# Wedding_Centerpiece_Controller_V1_2.net
KiCad netlist of a schematic drawn in EAGLE
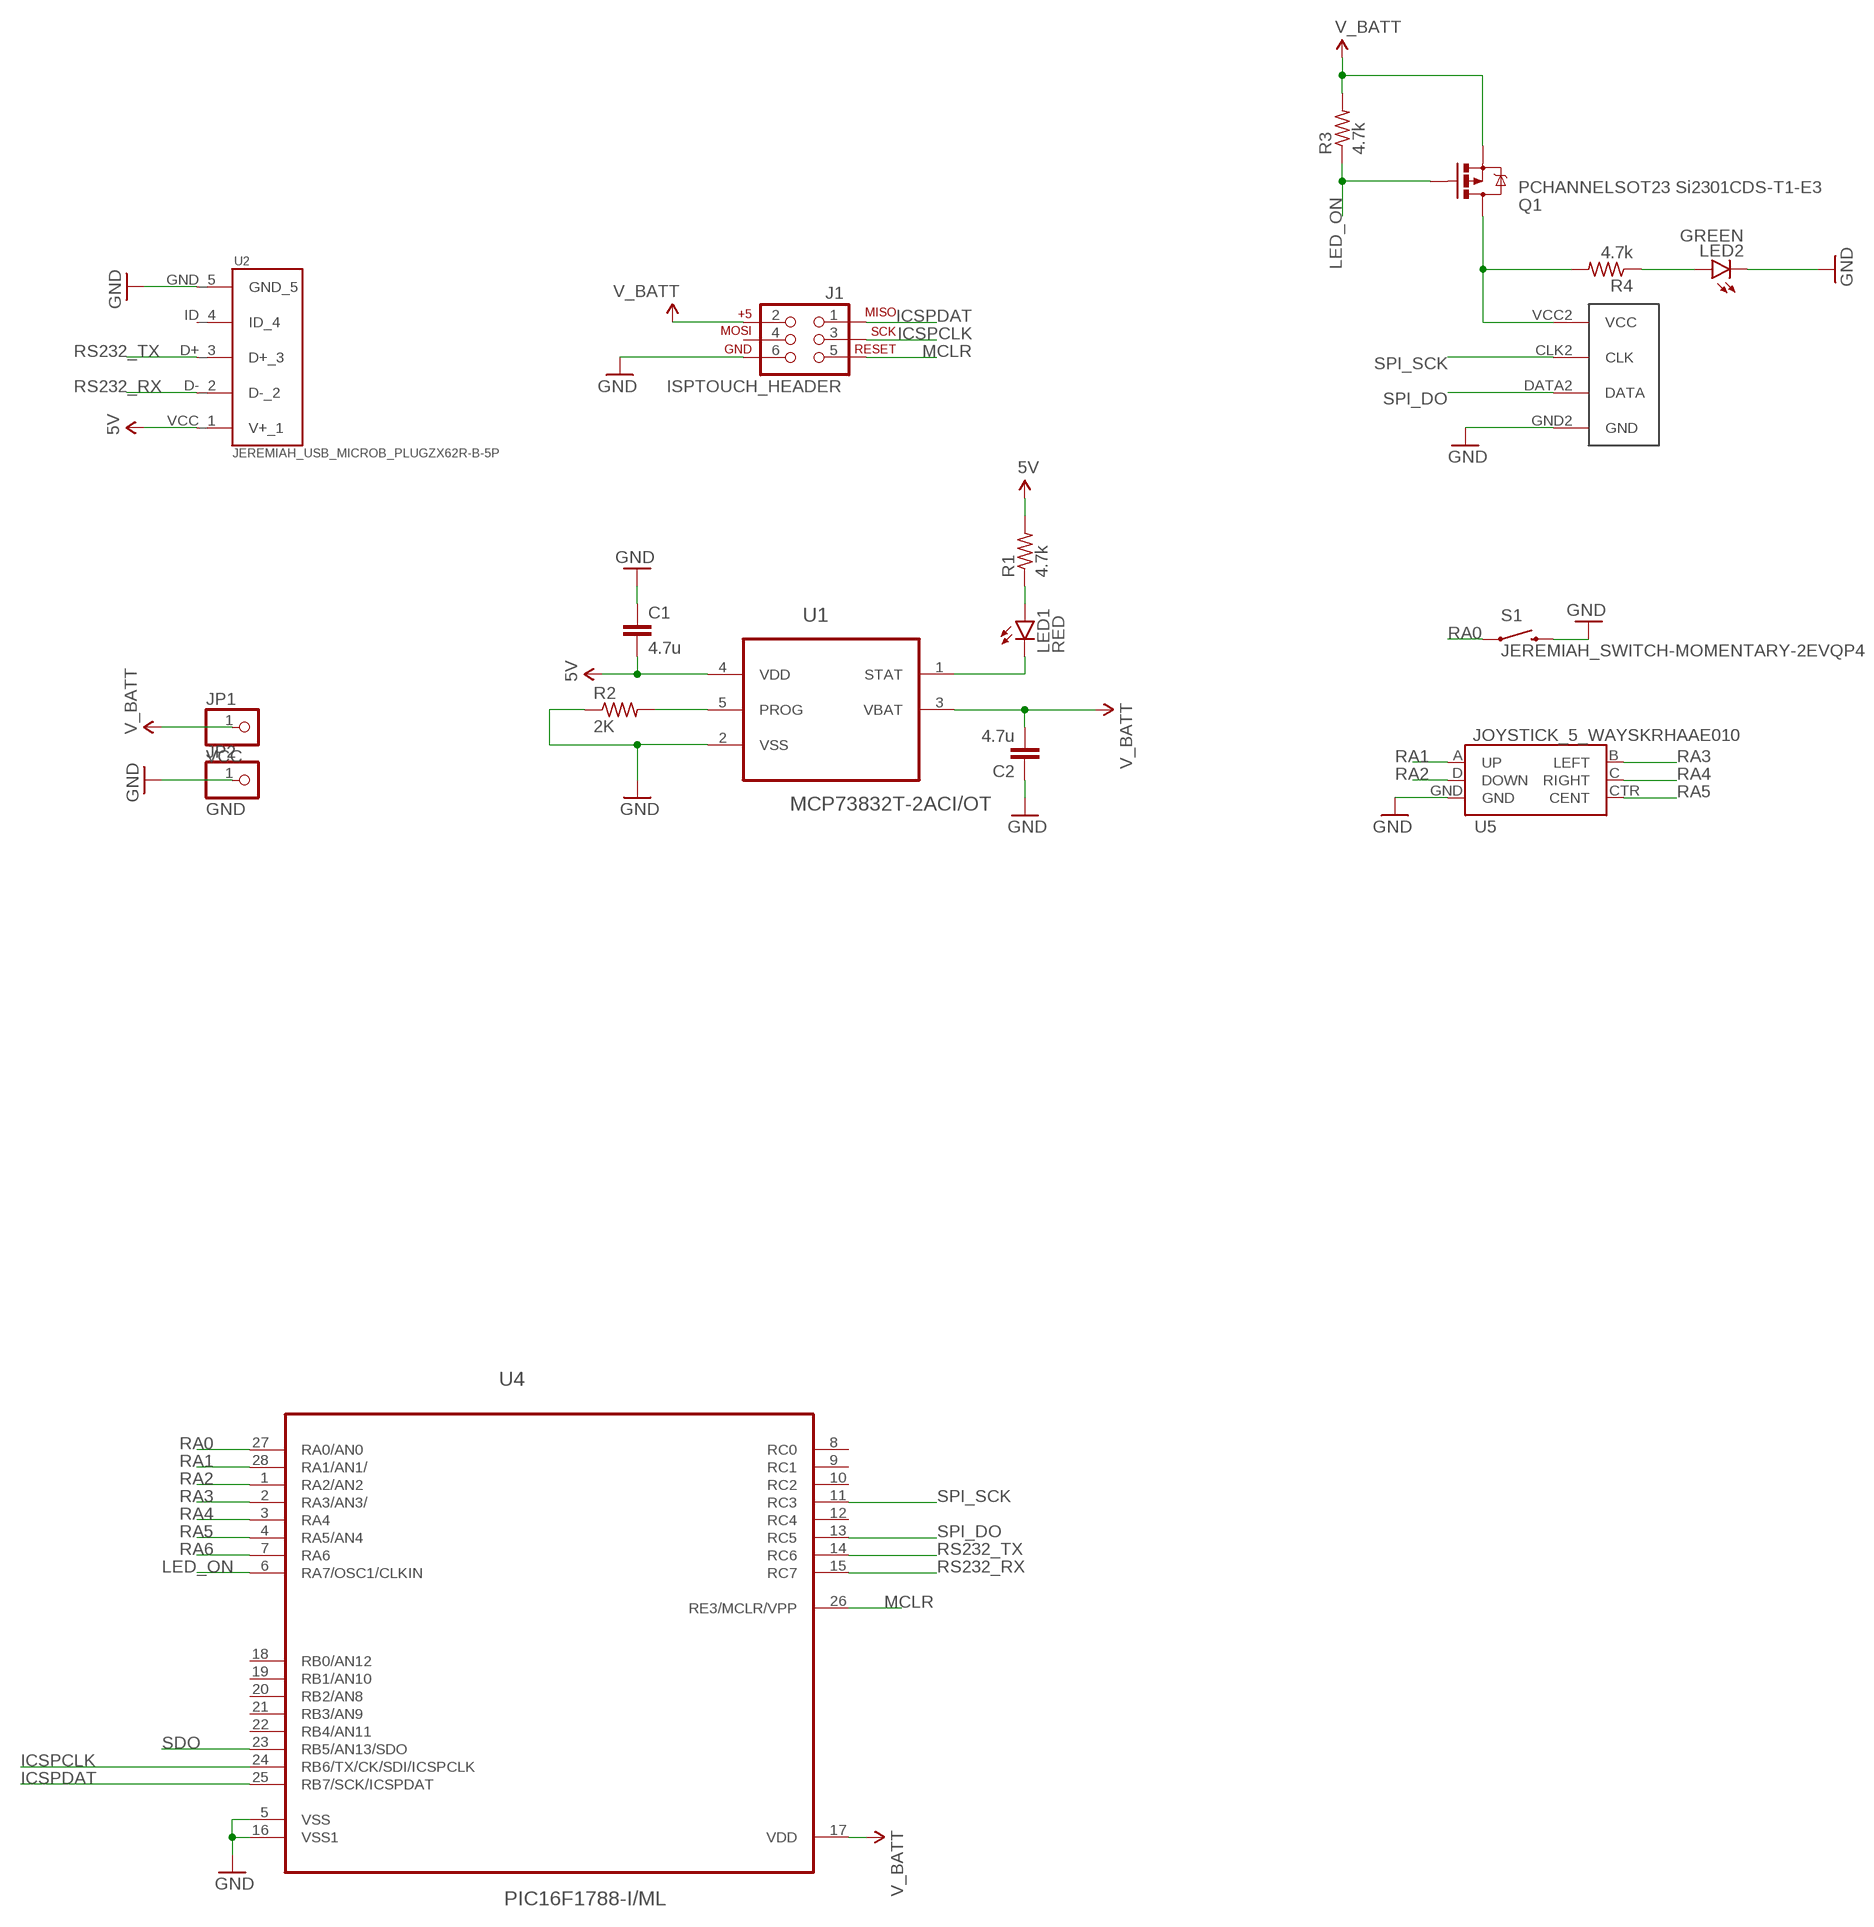
[diagram p0: schematic, sheet 1]

(export (version "E")
  (design (tool "Eeschema 10.0.6"))
  (components
    (comp (ref "C1")
      (value "4.7u")
      (footprint "eagle-import:0402-CAP")
      (libsource (lib "eagle-import") (part "CAP0402-CAP"))
    )
    (comp (ref "C2")
      (value "4.7u")
      (footprint "eagle-import:0402-CAP")
      (libsource (lib "eagle-import") (part "CAP0402-CAP"))
    )
    (comp (ref "J1")
      (value "ISPTOUCH_HEADER")
      (footprint "eagle-import:AVX_9188_6-WAY_MATING_GUIDE")
      (libsource (lib "eagle-import") (part "ISPTOUCH_HEADER"))
    )
    (comp (ref "JP1")
      (value "VCC")
      (footprint "eagle-import:1X01")
      (libsource (lib "eagle-import") (part "PINHD-1X1"))
    )
    (comp (ref "JP2")
      (value "GND")
      (footprint "eagle-import:1X01")
      (libsource (lib "eagle-import") (part "PINHD-1X1"))
    )
    (comp (ref "LED1")
      (value "RED")
      (footprint "eagle-import:LED-0603")
      (libsource (lib "eagle-import") (part "LED0603"))
    )
    (comp (ref "LED2")
      (value "GREEN")
      (footprint "eagle-import:LED-0603")
      (libsource (lib "eagle-import") (part "LED0603"))
    )
    (comp (ref "Q1")
      (value "PCHANNELSOT23 Si2301CDS-T1-E3")
      (footprint "eagle-import:JEREMIAH_SOT23")
      (libsource (lib "eagle-import") (part "JEREMIAH_MOSFET-PCHANNELSOT23"))
    )
    (comp (ref "R1")
      (value "4.7k")
      (footprint "eagle-import:R0402")
      (libsource (lib "eagle-import") (part "R-US_R0402"))
    )
    (comp (ref "R2")
      (value "2K")
      (footprint "eagle-import:R0402")
      (libsource (lib "eagle-import") (part "R-US_R0402"))
    )
    (comp (ref "R3")
      (value "4.7k")
      (footprint "eagle-import:R0402")
      (libsource (lib "eagle-import") (part "R-US_R0402"))
    )
    (comp (ref "R4")
      (value "4.7k")
      (footprint "eagle-import:R0402")
      (libsource (lib "eagle-import") (part "R-US_R0402"))
    )
    (comp (ref "S1")
      (value "JEREMIAH_SWITCH-MOMENTARY-2EVQP4")
      (footprint "eagle-import:JEREMIAH_EVQP4_SWITCH")
      (libsource (lib "eagle-import") (part "JEREMIAH_SWITCH-MOMENTARY-2EVQP4"))
    )
    (comp (ref "U1")
      (value "MCP73832T-2ACI/OT")
      (footprint "eagle-import:SOT95P280X145-5N")
      (libsource (lib "eagle-import") (part "MCP73832T-2ACI/OT"))
    )
    (comp (ref "U2")
      (value "JEREMIAH_USB_MICROB_PLUGZX62R-B-5P")
      (footprint "eagle-import:JEREMIAH_USB_MICRO_ZX62R-B-5P")
      (libsource (lib "eagle-import") (part "JEREMIAH_USB_MICROB_PLUGZX62R-B-5P"))
    )
    (comp (ref "U3")
      (value "JEREMIAH_LED_STRIP_WS2801CLENLED_2L_BEGIN")
      (footprint "eagle-import:JEREMIAH_LED_STRIP_WS2801_CLENLED_2L_BEGIN")
      (libsource (lib "eagle-import") (part "JEREMIAH_LED_STRIP_WS2801CLENLED_2L_BEGIN"))
    )
    (comp (ref "U4")
      (value "PIC16F1788-I/ML")
      (footprint "eagle-import:QFN65P600X600X100-29N")
      (libsource (lib "eagle-import") (part "PIC16F1788-I/ML"))
    )
    (comp (ref "U5")
      (value "JOYSTICK_5_WAYSKRHAAE010")
      (footprint "eagle-import:ALPS_SKRHAAE010")
      (libsource (lib "eagle-import") (part "JOYSTICK_5_WAYSKRHAAE010"))
    )
  )
  (nets
    (net (code "1") (name "/ICSPCLK") (class "Default")
      (node (ref "J1") (pin "3") (pinfunction "3_3") (pintype "passive"))
      (node (ref "U4") (pin "24") (pinfunction "RB6/TX/CK/SDI/ICSPCLK_24") (pintype "bidirectional"))
    )
    (net (code "2") (name "/ICSPDAT") (class "Default")
      (node (ref "J1") (pin "1") (pinfunction "1_1") (pintype "passive"))
      (node (ref "U4") (pin "25") (pinfunction "RB7/SCK/ICSPDAT_25") (pintype "bidirectional"))
    )
    (net (code "3") (name "/LED_ON") (class "Default")
      (node (ref "Q1") (pin "1") (pinfunction "G_1") (pintype "passive"))
      (node (ref "R3") (pin "1") (pinfunction "1_1") (pintype "passive"))
      (node (ref "U4") (pin "6") (pinfunction "RA7/OSC1/CLKIN_6") (pintype "bidirectional"))
    )
    (net (code "4") (name "/MCLR") (class "Default")
      (node (ref "J1") (pin "5") (pinfunction "5_5") (pintype "passive"))
      (node (ref "U4") (pin "26") (pinfunction "RE3/MCLR/VPP_26") (pintype "bidirectional"))
    )
    (net (code "5") (name "/RA0") (class "Default")
      (node (ref "S1") (pin "1") (pinfunction "1_1") (pintype "passive"))
      (node (ref "U4") (pin "27") (pinfunction "RA0/AN0_27") (pintype "bidirectional"))
    )
    (net (code "6") (name "/RA1") (class "Default")
      (node (ref "U4") (pin "28") (pinfunction "RA1/AN1/_28") (pintype "bidirectional"))
      (node (ref "U5") (pin "A") (pinfunction "UP_A") (pintype "bidirectional"))
    )
    (net (code "7") (name "/RA2") (class "Default")
      (node (ref "U4") (pin "1") (pinfunction "RA2/AN2_1") (pintype "bidirectional"))
      (node (ref "U5") (pin "D") (pinfunction "DOWN_D") (pintype "bidirectional"))
    )
    (net (code "8") (name "/RA3") (class "Default")
      (node (ref "U4") (pin "2") (pinfunction "RA3/AN3/_2") (pintype "bidirectional"))
      (node (ref "U5") (pin "B") (pinfunction "LEFT_B") (pintype "bidirectional"))
    )
    (net (code "9") (name "/RA4") (class "Default")
      (node (ref "U4") (pin "3") (pinfunction "RA4_3") (pintype "bidirectional"))
      (node (ref "U5") (pin "C") (pinfunction "RIGHT_C") (pintype "bidirectional"))
    )
    (net (code "10") (name "/RA5") (class "Default")
      (node (ref "U4") (pin "4") (pinfunction "RA5/AN4_4") (pintype "input"))
      (node (ref "U5") (pin "CTR") (pinfunction "CENT_CTR") (pintype "bidirectional"))
    )
    (net (code "11") (name "/RA6") (class "Default")
      (node (ref "U4") (pin "7") (pinfunction "RA6_7") (pintype "bidirectional"))
    )
    (net (code "12") (name "/RS232_RX") (class "Default")
      (node (ref "U2") (pin "D-_2") (pinfunction "D-_2_D-_2") (pintype "bidirectional"))
      (node (ref "U4") (pin "15") (pinfunction "RC7_15") (pintype "bidirectional"))
    )
    (net (code "13") (name "/RS232_TX") (class "Default")
      (node (ref "U2") (pin "D+_3") (pinfunction "D+_3_D+_3") (pintype "bidirectional"))
      (node (ref "U4") (pin "14") (pinfunction "RC6_14") (pintype "bidirectional"))
    )
    (net (code "14") (name "/SDO") (class "Default")
      (node (ref "U4") (pin "23") (pinfunction "RB5/AN13/SDO_23") (pintype "bidirectional"))
    )
    (net (code "15") (name "/SPI_DO") (class "Default")
      (node (ref "U3") (pin "DATA2") (pinfunction "DATA_DATA2") (pintype "bidirectional"))
      (node (ref "U4") (pin "13") (pinfunction "RC5_13") (pintype "bidirectional"))
    )
    (net (code "16") (name "/SPI_SCK") (class "Default")
      (node (ref "U3") (pin "CLK2") (pinfunction "CLK_CLK2") (pintype "bidirectional"))
      (node (ref "U4") (pin "11") (pinfunction "RC3_11") (pintype "bidirectional"))
    )
    (net (code "17") (name "5V") (class "Default")
      (node (ref "C1") (pin "2") (pinfunction "2_2") (pintype "passive"))
      (node (ref "R1") (pin "2") (pinfunction "2_2") (pintype "passive"))
      (node (ref "U1") (pin "4") (pinfunction "VDD_4") (pintype "power_in"))
      (node (ref "U2") (pin "VCC_1") (pinfunction "V+_1_VCC_1") (pintype "bidirectional"))
    )
    (net (code "18") (name "GND") (class "Default")
      (node (ref "C1") (pin "1") (pinfunction "1_1") (pintype "passive"))
      (node (ref "C2") (pin "1") (pinfunction "1_1") (pintype "passive"))
      (node (ref "J1") (pin "6") (pinfunction "6_6") (pintype "passive"))
      (node (ref "JP2") (pin "1") (pinfunction "1_1") (pintype "passive"))
      (node (ref "LED2") (pin "C") (pinfunction "C_C") (pintype "passive"))
      (node (ref "R2") (pin "1") (pinfunction "1_1") (pintype "passive"))
      (node (ref "S1") (pin "2") (pinfunction "2_2") (pintype "passive"))
      (node (ref "U1") (pin "2") (pinfunction "VSS_2") (pintype "power_in"))
      (node (ref "U2") (pin "GND_5") (pinfunction "GND_5_GND_5") (pintype "bidirectional"))
      (node (ref "U3") (pin "GND2") (pinfunction "GND_GND2") (pintype "bidirectional"))
      (node (ref "U4") (pin "16") (pinfunction "VSS1_16") (pintype "power_in"))
      (node (ref "U4") (pin "5") (pinfunction "VSS_5") (pintype "power_in"))
      (node (ref "U5") (pin "GND") (pinfunction "GND_GND") (pintype "bidirectional"))
    )
    (net (code "19") (name "Net-(LED1-PadA)") (class "Default")
      (node (ref "LED1") (pin "A") (pinfunction "A_A") (pintype "passive"))
      (node (ref "R1") (pin "1") (pinfunction "1_1") (pintype "passive"))
    )
    (net (code "20") (name "Net-(LED2-PadA)") (class "Default")
      (node (ref "LED2") (pin "A") (pinfunction "A_A") (pintype "passive"))
      (node (ref "R4") (pin "1") (pinfunction "1_1") (pintype "passive"))
    )
    (net (code "21") (name "Net-(Q1-D)") (class "Default")
      (node (ref "Q1") (pin "3") (pinfunction "D_3") (pintype "passive"))
      (node (ref "R4") (pin "2") (pinfunction "2_2") (pintype "passive"))
      (node (ref "U3") (pin "VCC2") (pinfunction "VCC_VCC2") (pintype "bidirectional"))
    )
    (net (code "22") (name "Net-(U1-PROG)") (class "Default")
      (node (ref "R2") (pin "2") (pinfunction "2_2") (pintype "passive"))
      (node (ref "U1") (pin "5") (pinfunction "PROG_5") (pintype "input"))
    )
    (net (code "23") (name "Net-(U1-STAT)") (class "Default")
      (node (ref "LED1") (pin "C") (pinfunction "C_C") (pintype "passive"))
      (node (ref "U1") (pin "1") (pinfunction "STAT_1") (pintype "output"))
    )
    (net (code "24") (name "V_BATT") (class "Default")
      (node (ref "C2") (pin "2") (pinfunction "2_2") (pintype "passive"))
      (node (ref "J1") (pin "2") (pinfunction "2_2") (pintype "passive"))
      (node (ref "JP1") (pin "1") (pinfunction "1_1") (pintype "passive"))
      (node (ref "Q1") (pin "2") (pinfunction "S_2") (pintype "passive"))
      (node (ref "R3") (pin "2") (pinfunction "2_2") (pintype "passive"))
      (node (ref "U1") (pin "3") (pinfunction "VBAT_3") (pintype "output"))
      (node (ref "U4") (pin "17") (pinfunction "VDD_17") (pintype "power_in"))
    )
    (net (code "25") (name "unconnected-(J1-Pad4)") (class "Default")
      (node (ref "J1") (pin "4") (pinfunction "4_4") (pintype "passive"))
    )
    (net (code "26") (name "unconnected-(U2-PadID_4)") (class "Default")
      (node (ref "U2") (pin "ID_4") (pinfunction "ID_4_ID_4") (pintype "bidirectional"))
    )
    (net (code "27") (name "unconnected-(U4-RB0{slash}AN12-Pad18)") (class "Default")
      (node (ref "U4") (pin "18") (pinfunction "RB0/AN12_18") (pintype "bidirectional"))
    )
    (net (code "28") (name "unconnected-(U4-RB1{slash}AN10-Pad19)") (class "Default")
      (node (ref "U4") (pin "19") (pinfunction "RB1/AN10_19") (pintype "bidirectional"))
    )
    (net (code "29") (name "unconnected-(U4-RB2{slash}AN8-Pad20)") (class "Default")
      (node (ref "U4") (pin "20") (pinfunction "RB2/AN8_20") (pintype "bidirectional"))
    )
    (net (code "30") (name "unconnected-(U4-RB3{slash}AN9-Pad21)") (class "Default")
      (node (ref "U4") (pin "21") (pinfunction "RB3/AN9_21") (pintype "bidirectional"))
    )
    (net (code "31") (name "unconnected-(U4-RB4{slash}AN11-Pad22)") (class "Default")
      (node (ref "U4") (pin "22") (pinfunction "RB4/AN11_22") (pintype "bidirectional"))
    )
    (net (code "32") (name "unconnected-(U4-RC0-Pad8)") (class "Default")
      (node (ref "U4") (pin "8") (pinfunction "RC0_8") (pintype "bidirectional"))
    )
    (net (code "33") (name "unconnected-(U4-RC1-Pad9)") (class "Default")
      (node (ref "U4") (pin "9") (pinfunction "RC1_9") (pintype "bidirectional"))
    )
    (net (code "34") (name "unconnected-(U4-RC2-Pad10)") (class "Default")
      (node (ref "U4") (pin "10") (pinfunction "RC2_10") (pintype "bidirectional"))
    )
    (net (code "35") (name "unconnected-(U4-RC4-Pad12)") (class "Default")
      (node (ref "U4") (pin "12") (pinfunction "RC4_12") (pintype "bidirectional"))
    )
  )
)
